# RasBOB_board.net
KiCad netlist of a schematic drawn in Altium Designer
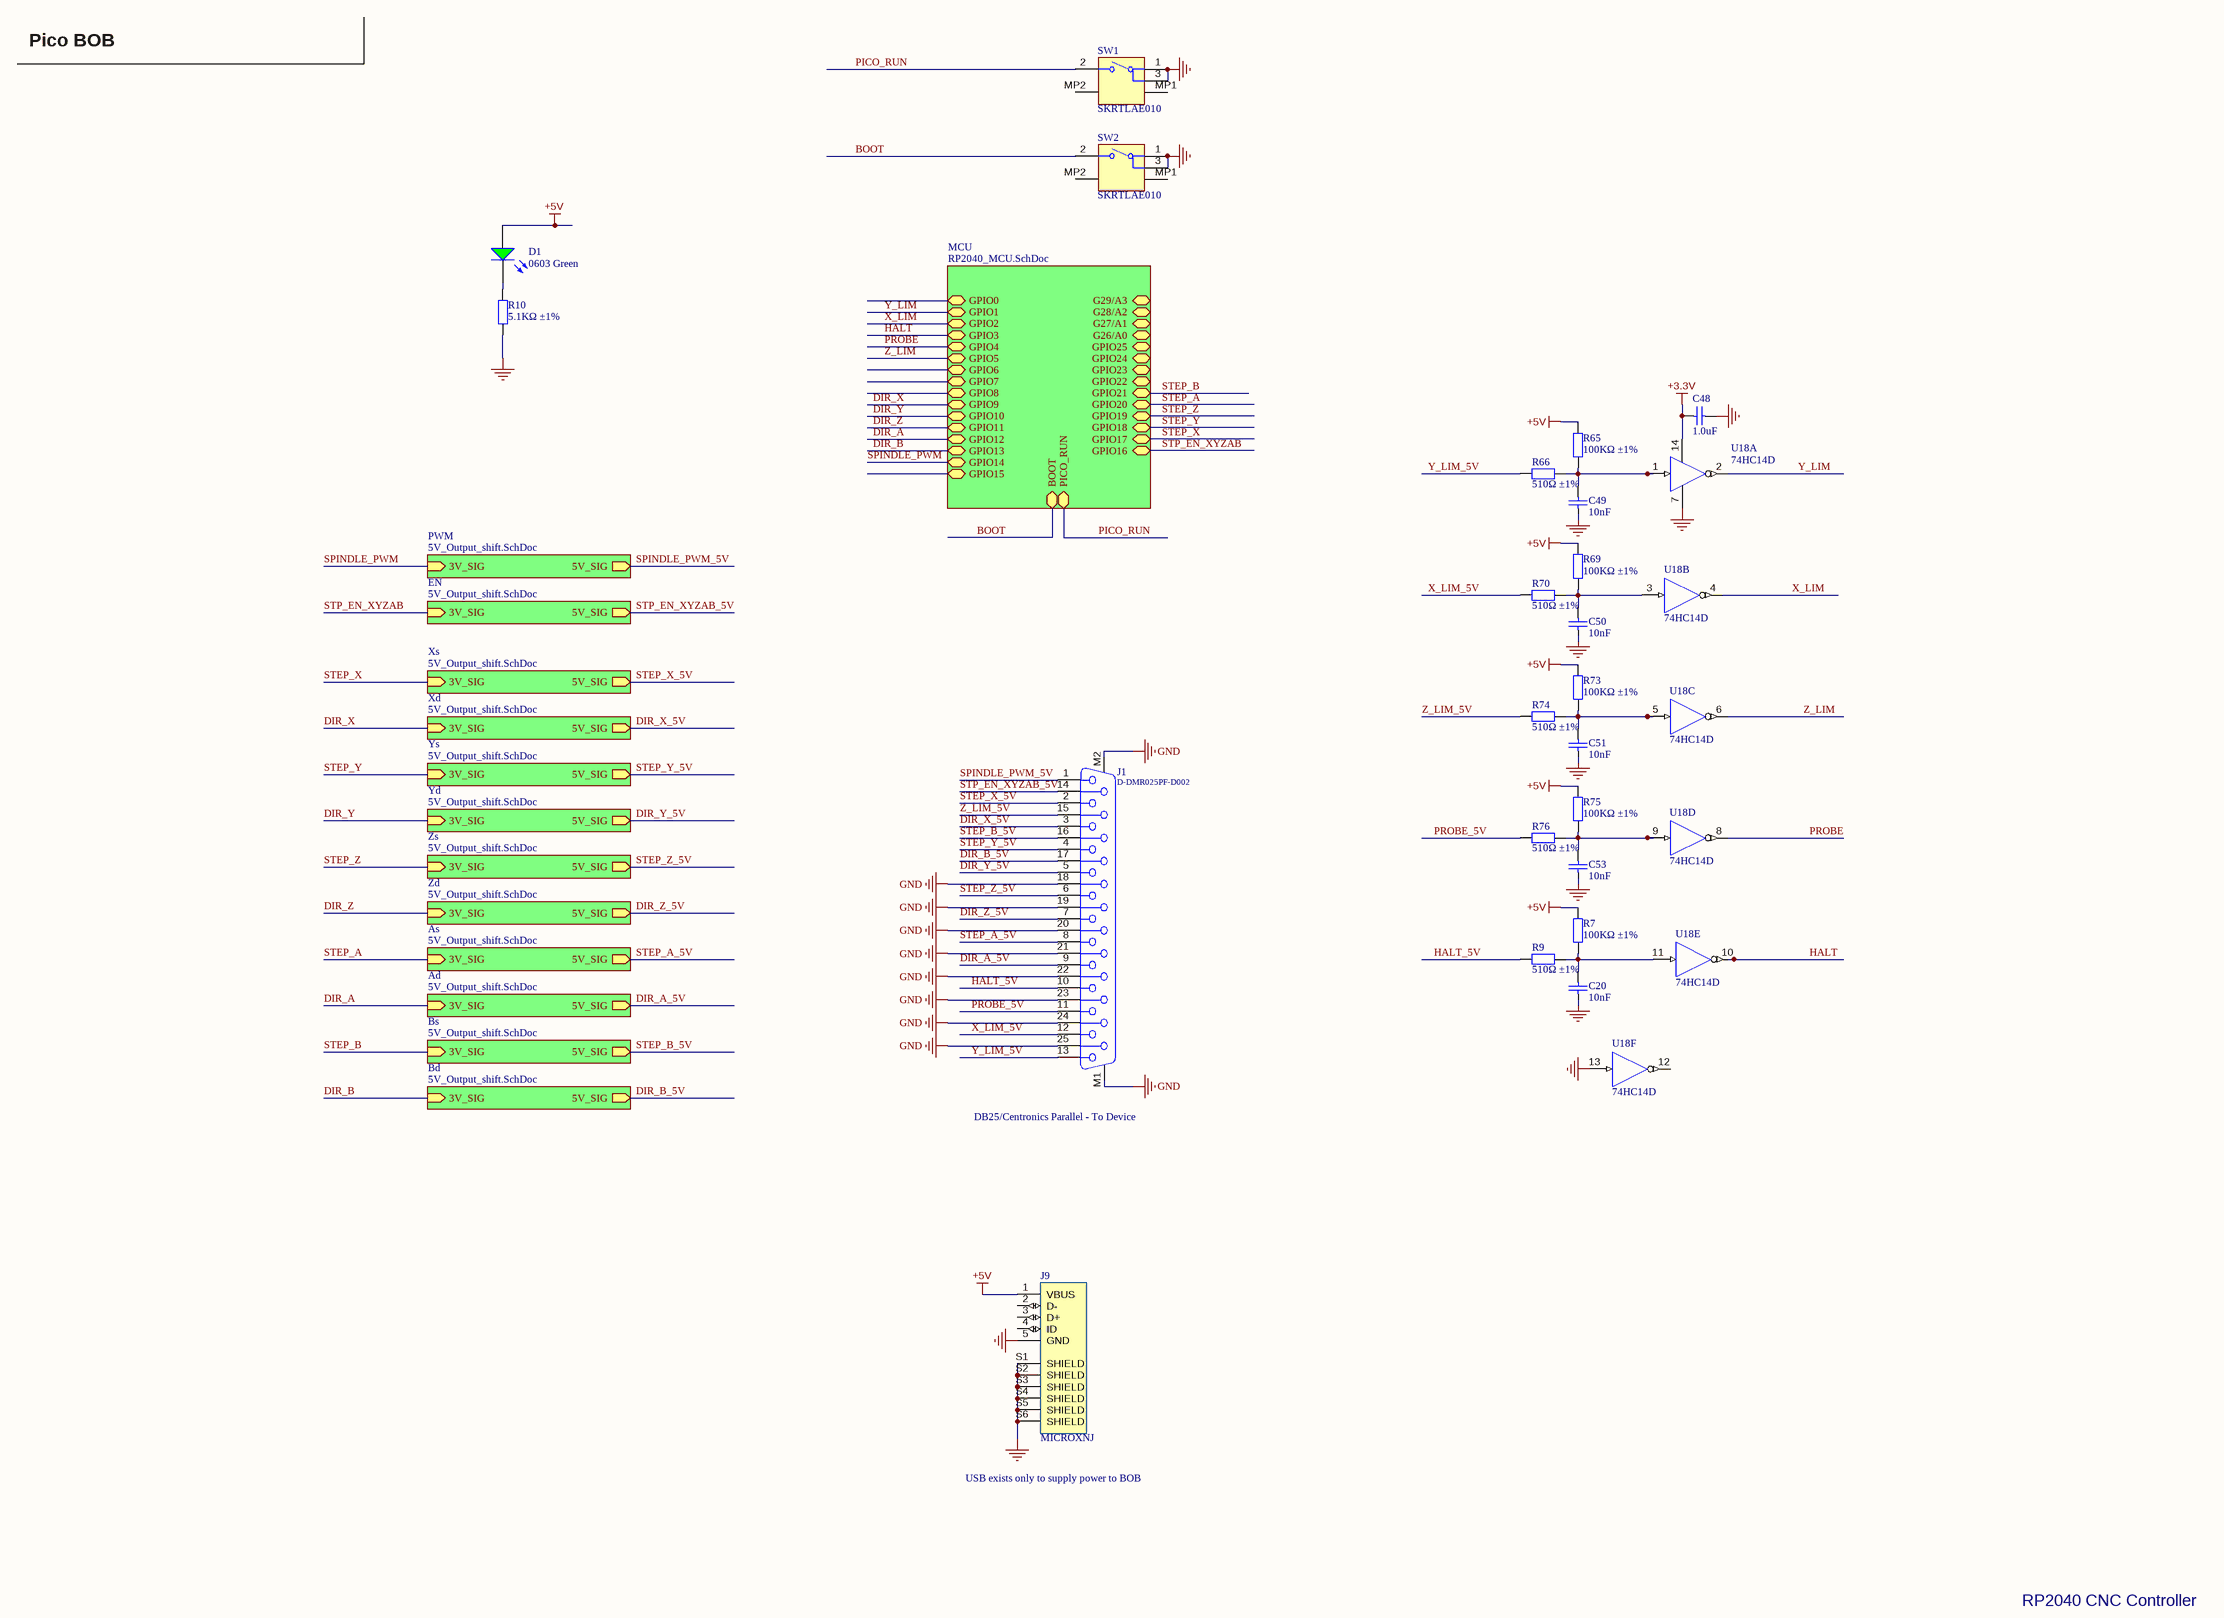
[diagram p0: RasBOB_board.SchDoc]

(export (version "E")
  (design (tool "Eeschema 10.0.6"))
  (components
    (comp (ref "C20")
      (value "10nF")
      (footprint "0402_C")
      (description "Chip capacitors")
      (fields
        (field (name "MANUFACTURER") "Samsung Electro-Mechanics")
        (field (name "PARTNUMBER") "CL05B103KB5NNNC")
      )
      (libsource (lib "Cap") (part "0402 10nF (103) 10% 50V"))
    )
    (comp (ref "C48")
      (value "1.0uF")
      (footprint "0402_C")
      (description "Chip capacitor")
      (fields
        (field (name "MANUFACTURER") "Samsung Electro-Mechanics")
        (field (name "PARTNUMBER") "CL05A105KA5NQNC")
      )
      (libsource (lib "Cap") (part "0402 1.0uF (105) 10% 25V"))
    )
    (comp (ref "C49")
      (value "10nF")
      (footprint "0402_C")
      (description "Chip capacitors")
      (fields
        (field (name "MANUFACTURER") "Samsung Electro-Mechanics")
        (field (name "PARTNUMBER") "CL05B103KB5NNNC")
      )
      (libsource (lib "Cap") (part "0402 10nF (103) 10% 50V"))
    )
    (comp (ref "C50")
      (value "10nF")
      (footprint "0402_C")
      (description "Chip capacitors")
      (fields
        (field (name "MANUFACTURER") "Samsung Electro-Mechanics")
        (field (name "PARTNUMBER") "CL05B103KB5NNNC")
      )
      (libsource (lib "Cap") (part "0402 10nF (103) 10% 50V"))
    )
    (comp (ref "C51")
      (value "10nF")
      (footprint "0402_C")
      (description "Chip capacitors")
      (fields
        (field (name "MANUFACTURER") "Samsung Electro-Mechanics")
        (field (name "PARTNUMBER") "CL05B103KB5NNNC")
      )
      (libsource (lib "Cap") (part "0402 10nF (103) 10% 50V"))
    )
    (comp (ref "C53")
      (value "10nF")
      (footprint "0402_C")
      (description "Chip capacitors")
      (fields
        (field (name "MANUFACTURER") "Samsung Electro-Mechanics")
        (field (name "PARTNUMBER") "CL05B103KB5NNNC")
      )
      (libsource (lib "Cap") (part "0402 10nF (103) 10% 50V"))
    )
    (comp (ref "D1")
      (value "0603 Green")
      (footprint "0603_LED_S1")
      (description "LED")
      (libsource (lib "LED") (part "0603 LED Green"))
    )
    (comp (ref "J1")
      (value "D-DMR025PF-D002")
      (footprint "618025231121")
      (description "Through Hole,P=2.77mm D-Sub Connectors ROHS")
      (libsource (lib "Altium Content Vault") (part "WE-CN-2S-2F-D25"))
    )
    (comp (ref "J9")
      (value "MICROXNJ")
      (footprint "SHOUHAN_MICROXNJ")
      (description "Micro USB")
      (fields (field (name "MF") "Shouhan"))
      (libsource (lib "Universal_CNC_Breakout") (part "MICROXNJ"))
    )
    (comp (ref "R7")
      (value "100KΩ ±1%")
      (footprint "0402_R")
      (description "Chip resistor")
      (fields (field (name "MANUFACTURER") "Uniroyal Elec") (field (name "PARTNUMBER") "0402WGF1003TCE"))
      (libsource (lib "RES") (part "0402 100K (1003) 1%"))
    )
    (comp (ref "R9")
      (value "510Ω ±1%")
      (footprint "0402_R")
      (description "Chip resistor")
      (fields (field (name "MANUFACTURER") "Uniroyal Elec") (field (name "PARTNUMBER") "0402WGF5100TCE"))
      (libsource (lib "RES") (part "0402 510R (5100) 1%"))
    )
    (comp (ref "R10")
      (value "5.1KΩ ±1%")
      (footprint "0402_R")
      (description "Chip resistor")
      (fields (field (name "MANUFACTURER") "Uniroyal Elec") (field (name "PARTNUMBER") "0402WGF5101TCE"))
      (libsource (lib "RES") (part "0402 5.1K (5101) 1%"))
    )
    (comp (ref "R65")
      (value "100KΩ ±1%")
      (footprint "0402_R")
      (description "Chip resistor")
      (fields (field (name "MANUFACTURER") "Uniroyal Elec") (field (name "PARTNUMBER") "0402WGF1003TCE"))
      (libsource (lib "RES") (part "0402 100K (1003) 1%"))
    )
    (comp (ref "R66")
      (value "510Ω ±1%")
      (footprint "0402_R")
      (description "Chip resistor")
      (fields (field (name "MANUFACTURER") "Uniroyal Elec") (field (name "PARTNUMBER") "0402WGF5100TCE"))
      (libsource (lib "RES") (part "0402 510R (5100) 1%"))
    )
    (comp (ref "R69")
      (value "100KΩ ±1%")
      (footprint "0402_R")
      (description "Chip resistor")
      (fields (field (name "MANUFACTURER") "Uniroyal Elec") (field (name "PARTNUMBER") "0402WGF1003TCE"))
      (libsource (lib "RES") (part "0402 100K (1003) 1%"))
    )
    (comp (ref "R70")
      (value "510Ω ±1%")
      (footprint "0402_R")
      (description "Chip resistor")
      (fields (field (name "MANUFACTURER") "Uniroyal Elec") (field (name "PARTNUMBER") "0402WGF5100TCE"))
      (libsource (lib "RES") (part "0402 510R (5100) 1%"))
    )
    (comp (ref "R73")
      (value "100KΩ ±1%")
      (footprint "0402_R")
      (description "Chip resistor")
      (fields (field (name "MANUFACTURER") "Uniroyal Elec") (field (name "PARTNUMBER") "0402WGF1003TCE"))
      (libsource (lib "RES") (part "0402 100K (1003) 1%"))
    )
    (comp (ref "R74")
      (value "510Ω ±1%")
      (footprint "0402_R")
      (description "Chip resistor")
      (fields (field (name "MANUFACTURER") "Uniroyal Elec") (field (name "PARTNUMBER") "0402WGF5100TCE"))
      (libsource (lib "RES") (part "0402 510R (5100) 1%"))
    )
    (comp (ref "R75")
      (value "100KΩ ±1%")
      (footprint "0402_R")
      (description "Chip resistor")
      (fields (field (name "MANUFACTURER") "Uniroyal Elec") (field (name "PARTNUMBER") "0402WGF1003TCE"))
      (libsource (lib "RES") (part "0402 100K (1003) 1%"))
    )
    (comp (ref "R76")
      (value "510Ω ±1%")
      (footprint "0402_R")
      (description "Chip resistor")
      (fields (field (name "MANUFACTURER") "Uniroyal Elec") (field (name "PARTNUMBER") "0402WGF5100TCE"))
      (libsource (lib "RES") (part "0402 510R (5100) 1%"))
    )
    (comp (ref "SW1")
      (value "SKRTLAE010")
      (footprint "ALPS-SKRTLAE010_V")
      (description "Side Push Type, 250 V, -40 to 90 degC, 3-Pin SMD, RoHS, Tape and Reel")
      (fields (field (name "MANUFACTURER") "ALPS"))
      (libsource (lib "Altium Content Vault") (part "SW_SPST-3_A"))
    )
    (comp (ref "SW2")
      (value "SKRTLAE010")
      (footprint "ALPS-SKRTLAE010_V")
      (description "Side Push Type, 250 V, -40 to 90 degC, 3-Pin SMD, RoHS, Tape and Reel")
      (fields (field (name "MANUFACTURER") "ALPS"))
      (libsource (lib "Altium Content Vault") (part "SW_SPST-3_A"))
    )
    (comp (ref "U18")
      (value "74HC14D")
      (footprint "SOIC-14_150mil")
      (description "74系列逻辑芯片")
      (libsource (lib "IC") (part "74HC14D_[C5605]"))
    )
  )
  (nets
    (net (code "1") (name "+3.3V") (class "Default")
      (node (ref "C48") (pin "1") (pinfunction "1_1") (pintype "passive"))
      (node (ref "U18") (pin "14") (pinfunction "VCC_14") (pintype "power_in"))
    )
    (net (code "2") (name "+5V") (class "Default")
      (node (ref "D1") (pin "A") (pinfunction "A_A") (pintype "passive"))
      (node (ref "J9") (pin "1") (pinfunction "VBUS_1") (pintype "power_in"))
      (node (ref "R65") (pin "2") (pinfunction "2_2") (pintype "passive"))
      (node (ref "R69") (pin "2") (pinfunction "2_2") (pintype "passive"))
      (node (ref "R7") (pin "2") (pinfunction "2_2") (pintype "passive"))
      (node (ref "R73") (pin "2") (pinfunction "2_2") (pintype "passive"))
      (node (ref "R75") (pin "2") (pinfunction "2_2") (pintype "passive"))
    )
    (net (code "3") (name "/BOOT") (class "Default")
      (node (ref "SW2") (pin "2") (pinfunction "2_2") (pintype "passive"))
    )
    (net (code "5") (name "/DIR_A_5V") (class "Default")
      (node (ref "J1") (pin "9") (pinfunction "9_9") (pintype "passive"))
    )
    (net (code "7") (name "/DIR_B_5V") (class "Default")
      (node (ref "J1") (pin "17") (pinfunction "17_17") (pintype "passive"))
    )
    (net (code "9") (name "/DIR_X_5V") (class "Default")
      (node (ref "J1") (pin "3") (pinfunction "3_3") (pintype "passive"))
    )
    (net (code "11") (name "/DIR_Y_5V") (class "Default")
      (node (ref "J1") (pin "5") (pinfunction "5_5") (pintype "passive"))
    )
    (net (code "13") (name "/DIR_Z_5V") (class "Default")
      (node (ref "J1") (pin "7") (pinfunction "7_7") (pintype "passive"))
    )
    (net (code "27") (name "/HALT") (class "Default")
      (node (ref "U18") (pin "10") (pinfunction "Y_10") (pintype "output"))
    )
    (net (code "28") (name "/HALT_5V") (class "Default")
      (node (ref "J1") (pin "10") (pinfunction "10_10") (pintype "passive"))
      (node (ref "R9") (pin "1") (pinfunction "1_1") (pintype "passive"))
    )
    (net (code "29") (name "/PICO_RUN") (class "Default")
      (node (ref "SW1") (pin "2") (pinfunction "2_2") (pintype "passive"))
    )
    (net (code "30") (name "/PROBE") (class "Default")
      (node (ref "U18") (pin "8") (pinfunction "Y_8") (pintype "output"))
    )
    (net (code "31") (name "/PROBE_5V") (class "Default")
      (node (ref "J1") (pin "11") (pinfunction "11_11") (pintype "passive"))
      (node (ref "R76") (pin "1") (pinfunction "1_1") (pintype "passive"))
    )
    (net (code "33") (name "/SPINDLE_PWM_5V") (class "Default")
      (node (ref "J1") (pin "1") (pinfunction "1_1") (pintype "passive"))
    )
    (net (code "35") (name "/STEP_A_5V") (class "Default")
      (node (ref "J1") (pin "8") (pinfunction "8_8") (pintype "passive"))
    )
    (net (code "37") (name "/STEP_B_5V") (class "Default")
      (node (ref "J1") (pin "16") (pinfunction "16_16") (pintype "passive"))
    )
    (net (code "39") (name "/STEP_X_5V") (class "Default")
      (node (ref "J1") (pin "2") (pinfunction "2_2") (pintype "passive"))
    )
    (net (code "41") (name "/STEP_Y_5V") (class "Default")
      (node (ref "J1") (pin "4") (pinfunction "4_4") (pintype "passive"))
    )
    (net (code "43") (name "/STEP_Z_5V") (class "Default")
      (node (ref "J1") (pin "6") (pinfunction "6_6") (pintype "passive"))
    )
    (net (code "45") (name "/STP_EN_XYZAB_5V") (class "Default")
      (node (ref "J1") (pin "14") (pinfunction "14_14") (pintype "passive"))
    )
    (net (code "46") (name "/X_LIM") (class "Default")
      (node (ref "U18") (pin "4") (pinfunction "Y_4") (pintype "output"))
    )
    (net (code "47") (name "/X_LIM_5V") (class "Default")
      (node (ref "J1") (pin "12") (pinfunction "12_12") (pintype "passive"))
      (node (ref "R70") (pin "1") (pinfunction "1_1") (pintype "passive"))
    )
    (net (code "48") (name "/Y_LIM") (class "Default")
      (node (ref "U18") (pin "2") (pinfunction "Y_2") (pintype "output"))
    )
    (net (code "49") (name "/Y_LIM_5V") (class "Default")
      (node (ref "J1") (pin "13") (pinfunction "13_13") (pintype "passive"))
      (node (ref "R66") (pin "1") (pinfunction "1_1") (pintype "passive"))
    )
    (net (code "50") (name "/Z_LIM") (class "Default")
      (node (ref "U18") (pin "6") (pinfunction "Y_6") (pintype "output"))
    )
    (net (code "51") (name "/Z_LIM_5V") (class "Default")
      (node (ref "J1") (pin "15") (pinfunction "15_15") (pintype "passive"))
      (node (ref "R74") (pin "1") (pinfunction "1_1") (pintype "passive"))
    )
    (net (code "52") (name "GND") (class "Default")
      (node (ref "C20") (pin "1") (pinfunction "1_1") (pintype "passive"))
      (node (ref "C48") (pin "2") (pinfunction "2_2") (pintype "passive"))
      (node (ref "C49") (pin "1") (pinfunction "1_1") (pintype "passive"))
      (node (ref "C50") (pin "1") (pinfunction "1_1") (pintype "passive"))
      (node (ref "C51") (pin "1") (pinfunction "1_1") (pintype "passive"))
      (node (ref "C53") (pin "1") (pinfunction "1_1") (pintype "passive"))
      (node (ref "J1") (pin "18") (pinfunction "18_18") (pintype "passive"))
      (node (ref "J1") (pin "19") (pinfunction "19_19") (pintype "passive"))
      (node (ref "J1") (pin "20") (pinfunction "20_20") (pintype "passive"))
      (node (ref "J1") (pin "21") (pinfunction "21_21") (pintype "passive"))
      (node (ref "J1") (pin "22") (pinfunction "22_22") (pintype "passive"))
      (node (ref "J1") (pin "23") (pinfunction "23_23") (pintype "passive"))
      (node (ref "J1") (pin "24") (pinfunction "24_24") (pintype "passive"))
      (node (ref "J1") (pin "25") (pinfunction "25_25") (pintype "passive"))
      (node (ref "J1") (pin "M1") (pinfunction "M1_M1") (pintype "passive"))
      (node (ref "J1") (pin "M2") (pinfunction "M2_M2") (pintype "passive"))
      (node (ref "J9") (pin "5") (pinfunction "GND_5") (pintype "power_in"))
      (node (ref "J9") (pin "S1") (pinfunction "SHIELD_S1") (pintype "passive"))
      (node (ref "J9") (pin "S2") (pinfunction "SHIELD_S2") (pintype "passive"))
      (node (ref "J9") (pin "S3") (pinfunction "SHIELD_S3") (pintype "passive"))
      (node (ref "J9") (pin "S4") (pinfunction "SHIELD_S4") (pintype "passive"))
      (node (ref "J9") (pin "S5") (pinfunction "SHIELD_S5") (pintype "passive"))
      (node (ref "J9") (pin "S6") (pinfunction "SHIELD_S6") (pintype "passive"))
      (node (ref "R10") (pin "2") (pinfunction "2_2") (pintype "passive"))
      (node (ref "SW1") (pin "1") (pinfunction "1_1") (pintype "passive"))
      (node (ref "SW1") (pin "3") (pinfunction "3_3") (pintype "passive"))
      (node (ref "SW2") (pin "1") (pinfunction "1_1") (pintype "passive"))
      (node (ref "SW2") (pin "3") (pinfunction "3_3") (pintype "passive"))
      (node (ref "U18") (pin "13") (pinfunction "A_13") (pintype "input"))
      (node (ref "U18") (pin "7") (pinfunction "GND_7") (pintype "power_in"))
    )
    (net (code "53") (name "Net-(D1-PadK)") (class "Default")
      (node (ref "D1") (pin "K") (pinfunction "K_K") (pintype "passive"))
      (node (ref "R10") (pin "1") (pinfunction "1_1") (pintype "passive"))
    )
    (net (code "54") (name "Net-(U18A-A)") (class "Default")
      (node (ref "C49") (pin "2") (pinfunction "2_2") (pintype "passive"))
      (node (ref "R65") (pin "1") (pinfunction "1_1") (pintype "passive"))
      (node (ref "R66") (pin "2") (pinfunction "2_2") (pintype "passive"))
      (node (ref "U18") (pin "1") (pinfunction "A_1") (pintype "input"))
    )
    (net (code "55") (name "Net-(U18B-A)") (class "Default")
      (node (ref "C50") (pin "2") (pinfunction "2_2") (pintype "passive"))
      (node (ref "R69") (pin "1") (pinfunction "1_1") (pintype "passive"))
      (node (ref "R70") (pin "2") (pinfunction "2_2") (pintype "passive"))
      (node (ref "U18") (pin "3") (pinfunction "A_3") (pintype "input"))
    )
    (net (code "56") (name "Net-(U18C-A)") (class "Default")
      (node (ref "C51") (pin "2") (pinfunction "2_2") (pintype "passive"))
      (node (ref "R73") (pin "1") (pinfunction "1_1") (pintype "passive"))
      (node (ref "R74") (pin "2") (pinfunction "2_2") (pintype "passive"))
      (node (ref "U18") (pin "5") (pinfunction "A_5") (pintype "input"))
    )
    (net (code "57") (name "Net-(U18D-A)") (class "Default")
      (node (ref "C53") (pin "2") (pinfunction "2_2") (pintype "passive"))
      (node (ref "R75") (pin "1") (pinfunction "1_1") (pintype "passive"))
      (node (ref "R76") (pin "2") (pinfunction "2_2") (pintype "passive"))
      (node (ref "U18") (pin "9") (pinfunction "A_9") (pintype "input"))
    )
    (net (code "58") (name "Net-(U18E-A)") (class "Default")
      (node (ref "C20") (pin "2") (pinfunction "2_2") (pintype "passive"))
      (node (ref "R7") (pin "1") (pinfunction "1_1") (pintype "passive"))
      (node (ref "R9") (pin "2") (pinfunction "2_2") (pintype "passive"))
      (node (ref "U18") (pin "11") (pinfunction "A_11") (pintype "input"))
    )
    (net (code "59") (name "VDD") (class "Default")
      (node (ref "U18") (pin "14") (pinfunction "VDD_14") (pintype "power_in"))
    )
    (net (code "60") (name "unconnected-(J9-D+-Pad3)") (class "Default")
      (node (ref "J9") (pin "3") (pinfunction "D+_3") (pintype "bidirectional"))
    )
    (net (code "61") (name "unconnected-(J9-D--Pad2)") (class "Default")
      (node (ref "J9") (pin "2") (pinfunction "D-_2") (pintype "bidirectional"))
    )
    (net (code "62") (name "unconnected-(J9-ID-Pad4)") (class "Default")
      (node (ref "J9") (pin "4") (pinfunction "ID_4") (pintype "bidirectional"))
    )
    (net (code "63") (name "unconnected-(SW1-PadMP1)") (class "Default")
      (node (ref "SW1") (pin "MP1") (pinfunction "MP1_MP1") (pintype "passive"))
    )
    (net (code "64") (name "unconnected-(SW1-PadMP2)") (class "Default")
      (node (ref "SW1") (pin "MP2") (pinfunction "MP2_MP2") (pintype "passive"))
    )
    (net (code "65") (name "unconnected-(SW2-PadMP1)") (class "Default")
      (node (ref "SW2") (pin "MP1") (pinfunction "MP1_MP1") (pintype "passive"))
    )
    (net (code "66") (name "unconnected-(SW2-PadMP2)") (class "Default")
      (node (ref "SW2") (pin "MP2") (pinfunction "MP2_MP2") (pintype "passive"))
    )
    (net (code "67") (name "unconnected-(U18F-Y-Pad12)") (class "Default")
      (node (ref "U18") (pin "12") (pinfunction "Y_12") (pintype "output"))
    )
  )
)
